# Deel_4_op_amp.net
KiCad netlist of a schematic drawn in Altium Designer
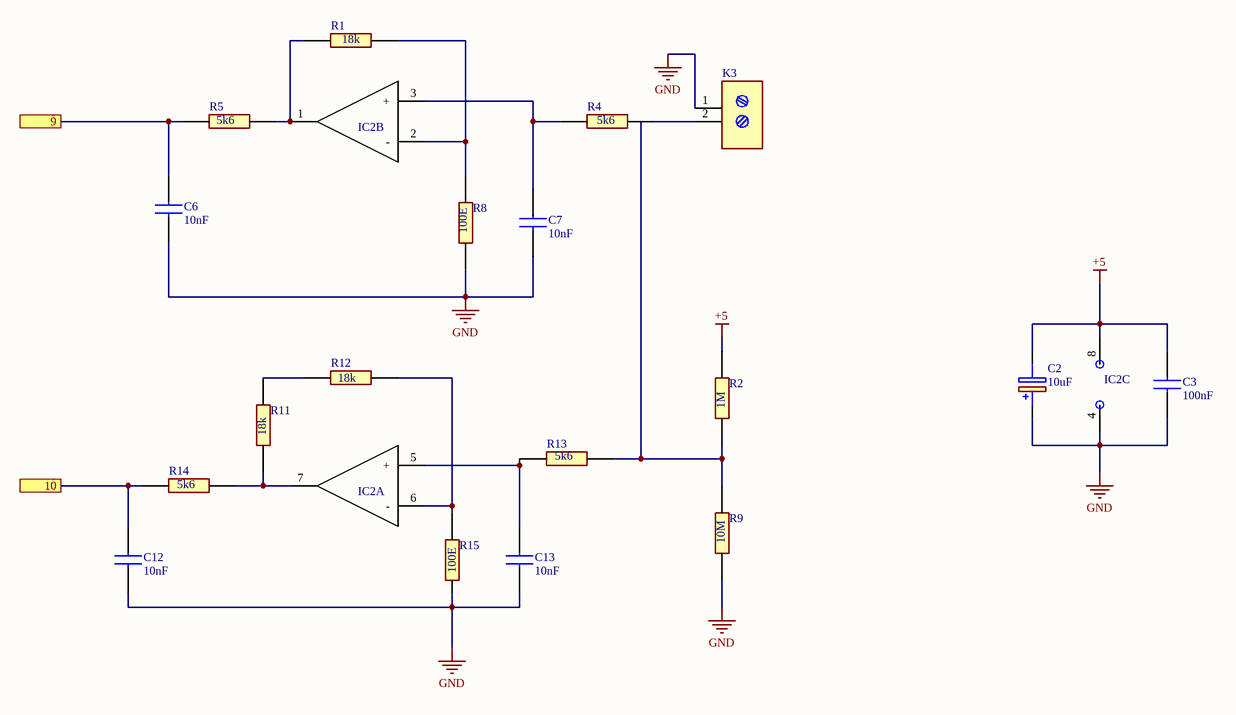
[diagram p0: Deel_4_op_amp.SchDoc]

(export (version "E")
  (design (tool "Eeschema 10.0.6"))
  (components
    (comp (ref "C2")
      (value "10uF")
      (footprint "PcbLib1:10uf")
      (description "Capacitor Polarised 860020672010")
      (fields
        (field (name "MOUSER2 PART NUMBER") "710-860020672010")
        (field (name "MANUFACTURER_PART_NUMBER") "860020672010")
      )
      (libsource (lib "Schlib_soldeerstation") (part "10uF"))
    )
    (comp (ref "C3")
      (value "100nF")
      (footprint "PcbLib1:100nF")
      (description "Capacitor")
      (fields
        (field (name "MANUFACTURER_PART_NUMBER") "0402YC104MAT2A")
        (field (name "MOUSER PART NUMBER") "581-0402YC104MAT2A")
      )
      (libsource (lib "Schlib_soldeerstation") (part "100nF"))
    )
    (comp (ref "C6")
      (value "10nF")
      (footprint "PcbLib1:10nF")
      (description "Capacitor")
      (fields
        (field (name "MANUFACTURER_PART_NUMBER") "0402YC104MAT2A")
        (field (name "MOUSER PART NUMBER") "581-0402YC104MAT2A")
      )
      (libsource (lib "Schlib_soldeerstation") (part "10nF"))
    )
    (comp (ref "C7")
      (value "10nF")
      (footprint "PcbLib1:10nF")
      (description "Capacitor")
      (fields
        (field (name "MANUFACTURER_PART_NUMBER") "0402YC104MAT2A")
        (field (name "MOUSER PART NUMBER") "581-0402YC104MAT2A")
      )
      (libsource (lib "Schlib_soldeerstation") (part "10nF"))
    )
    (comp (ref "C12")
      (value "10nF")
      (footprint "PcbLib1:10nF")
      (description "Capacitor")
      (fields
        (field (name "MANUFACTURER_PART_NUMBER") "0402YC104MAT2A")
        (field (name "MOUSER PART NUMBER") "581-0402YC104MAT2A")
      )
      (libsource (lib "Schlib_soldeerstation") (part "10nF"))
    )
    (comp (ref "C13")
      (value "10nF")
      (footprint "PcbLib1:10nF")
      (description "Capacitor")
      (fields
        (field (name "MANUFACTURER_PART_NUMBER") "0402YC104MAT2A")
        (field (name "MOUSER PART NUMBER") "581-0402YC104MAT2A")
      )
      (libsource (lib "Schlib_soldeerstation") (part "10nF"))
    )
    (comp (ref "IC2")
      (value "MCP6002-E_P dual opamp")
      (footprint "PcbLib1:mcp6002")
      (description "Integrated Circuit")
      (fields
        (field (name "MOUSER2 PART NUMBER") "579-MCP6002-E/P")
        (field (name "MANUFACTURER_PART_NUMBER") "MCP6002-E/P")
      )
      (libsource (lib "Schlib_soldeerstation") (part "MCP6002-E_P dual opamp"))
    )
    (comp (ref "K3")
      (value "schroefconnector")
      (footprint "PcbLib1:schroefconnector")
      (description "Connector 1716020000")
      (fields (field (name "MANUFACTURER_PART_NUMBER") "1716020000"))
      (libsource (lib "Schlib_soldeerstation") (part "schroefconnector"))
    )
    (comp (ref "R1")
      (value "18k")
      (footprint "PcbLib1:18k")
      (description "Resistor")
      (fields
        (field (name "MANUFACTURER_PART_NUMBER") "CPF0805B100RE1")
        (field (name "MOUSER PART NUMBER") "279-CPF0805B100RE1")
      )
      (libsource (lib "Schlib_soldeerstation") (part "18k"))
    )
    (comp (ref "R2")
      (value "1M")
      (footprint "PcbLib1:1M")
      (description "Resistor")
      (fields
        (field (name "MANUFACTURER_PART_NUMBER") "CPF0805B100RE1")
        (field (name "MOUSER PART NUMBER") "279-CPF0805B100RE1")
      )
      (libsource (lib "Schlib_soldeerstation") (part "1M"))
    )
    (comp (ref "R4")
      (value "5k6")
      (footprint "PcbLib1:5k6")
      (description "Resistor")
      (fields
        (field (name "MANUFACTURER_PART_NUMBER") "CPF0805B100RE1")
        (field (name "MOUSER PART NUMBER") "279-CPF0805B100RE1")
      )
      (libsource (lib "Schlib_soldeerstation") (part "5k6"))
    )
    (comp (ref "R5")
      (value "5k6")
      (footprint "PcbLib1:5k6")
      (description "Resistor")
      (fields
        (field (name "MANUFACTURER_PART_NUMBER") "CPF0805B100RE1")
        (field (name "MOUSER PART NUMBER") "279-CPF0805B100RE1")
      )
      (libsource (lib "Schlib_soldeerstation") (part "5k6"))
    )
    (comp (ref "R8")
      (value "100E")
      (footprint "PcbLib1:100ohm")
      (description "Resistor")
      (fields
        (field (name "MANUFACTURER_PART_NUMBER") "CPF0805B100RE1")
        (field (name "MOUSER PART NUMBER") "279-CPF0805B100RE1")
      )
      (libsource (lib "Schlib_soldeerstation") (part "100ohm"))
    )
    (comp (ref "R9")
      (value "10M")
      (footprint "PcbLib1:10M")
      (description "Resistor")
      (fields
        (field (name "MANUFACTURER_PART_NUMBER") "CPF0805B100RE1")
        (field (name "MOUSER PART NUMBER") "279-CPF0805B100RE1")
      )
      (libsource (lib "Schlib_soldeerstation") (part "10M"))
    )
    (comp (ref "R11")
      (value "18k")
      (footprint "PcbLib1:18k")
      (description "Resistor")
      (fields
        (field (name "MANUFACTURER_PART_NUMBER") "CPF0805B100RE1")
        (field (name "MOUSER PART NUMBER") "279-CPF0805B100RE1")
      )
      (libsource (lib "") (part "18k_1"))
    )
    (comp (ref "R12")
      (value "18k")
      (footprint "PcbLib1:18k")
      (description "Resistor")
      (fields
        (field (name "MANUFACTURER_PART_NUMBER") "CPF0805B100RE1")
        (field (name "MOUSER PART NUMBER") "279-CPF0805B100RE1")
      )
      (libsource (lib "Schlib_soldeerstation") (part "18k"))
    )
    (comp (ref "R13")
      (value "5k6")
      (footprint "PcbLib1:5k6")
      (description "Resistor")
      (fields
        (field (name "MANUFACTURER_PART_NUMBER") "CPF0805B100RE1")
        (field (name "MOUSER PART NUMBER") "279-CPF0805B100RE1")
      )
      (libsource (lib "Schlib_soldeerstation") (part "5k6"))
    )
    (comp (ref "R14")
      (value "5k6")
      (footprint "PcbLib1:5k6")
      (description "Resistor")
      (fields
        (field (name "MANUFACTURER_PART_NUMBER") "CPF0805B100RE1")
        (field (name "MOUSER PART NUMBER") "279-CPF0805B100RE1")
      )
      (libsource (lib "Schlib_soldeerstation") (part "5k6"))
    )
    (comp (ref "R15")
      (value "100E")
      (footprint "PcbLib1:100ohm")
      (description "Resistor")
      (fields
        (field (name "MANUFACTURER_PART_NUMBER") "CPF0805B100RE1")
        (field (name "MOUSER PART NUMBER") "279-CPF0805B100RE1")
      )
      (libsource (lib "Schlib_soldeerstation") (part "100ohm"))
    )
  )
  (nets
    (net (code "1") (name "+5") (class "Default")
      (node (ref "C2") (pin "2") (pinfunction "-_2") (pintype "passive"))
      (node (ref "C3") (pin "2") (pinfunction "2_2") (pintype "passive"))
      (node (ref "R2") (pin "2") (pinfunction "2_2") (pintype "passive"))
    )
    (net (code "2") (name "/9") (class "Default")
      (node (ref "C6") (pin "2") (pinfunction "2_2") (pintype "passive"))
      (node (ref "R5") (pin "1") (pinfunction "1_1") (pintype "passive"))
    )
    (net (code "3") (name "/10") (class "Default")
      (node (ref "C12") (pin "2") (pinfunction "2_2") (pintype "passive"))
      (node (ref "R14") (pin "1") (pinfunction "1_1") (pintype "passive"))
    )
    (net (code "4") (name "GND") (class "Default")
      (node (ref "C12") (pin "1") (pinfunction "1_1") (pintype "passive"))
      (node (ref "C13") (pin "1") (pinfunction "1_1") (pintype "passive"))
      (node (ref "C2") (pin "1") (pinfunction "+_1") (pintype "passive"))
      (node (ref "C3") (pin "1") (pinfunction "1_1") (pintype "passive"))
      (node (ref "C6") (pin "1") (pinfunction "1_1") (pintype "passive"))
      (node (ref "C7") (pin "1") (pinfunction "1_1") (pintype "passive"))
      (node (ref "K3") (pin "1") (pinfunction "1_1") (pintype "passive"))
      (node (ref "R15") (pin "1") (pinfunction "1_1") (pintype "passive"))
      (node (ref "R8") (pin "1") (pinfunction "1_1") (pintype "passive"))
      (node (ref "R9") (pin "1") (pinfunction "1_1") (pintype "passive"))
    )
    (net (code "5") (name "Net-(IC2A-+)") (class "Default")
      (node (ref "C13") (pin "2") (pinfunction "2_2") (pintype "passive"))
      (node (ref "IC2") (pin "5") (pinfunction "+_5") (pintype "passive"))
      (node (ref "R13") (pin "1") (pinfunction "1_1") (pintype "passive"))
    )
    (net (code "6") (name "Net-(IC2A--)") (class "Default")
      (node (ref "IC2") (pin "6") (pinfunction "-_6") (pintype "passive"))
      (node (ref "R12") (pin "2") (pinfunction "2_2") (pintype "passive"))
      (node (ref "R15") (pin "2") (pinfunction "2_2") (pintype "passive"))
    )
    (net (code "7") (name "Net-(IC2A-VOUTB)") (class "Default")
      (node (ref "IC2") (pin "7") (pinfunction "VOUTB_7") (pintype "passive"))
      (node (ref "R11") (pin "1") (pinfunction "1_1") (pintype "passive"))
      (node (ref "R14") (pin "2") (pinfunction "2_2") (pintype "passive"))
    )
    (net (code "8") (name "Net-(IC2B-+)") (class "Default")
      (node (ref "C7") (pin "2") (pinfunction "2_2") (pintype "passive"))
      (node (ref "IC2") (pin "3") (pinfunction "+_3") (pintype "passive"))
      (node (ref "R4") (pin "1") (pinfunction "1_1") (pintype "passive"))
    )
    (net (code "9") (name "Net-(IC2B--)") (class "Default")
      (node (ref "IC2") (pin "2") (pinfunction "-_2") (pintype "passive"))
      (node (ref "R1") (pin "2") (pinfunction "2_2") (pintype "passive"))
      (node (ref "R8") (pin "2") (pinfunction "2_2") (pintype "passive"))
    )
    (net (code "10") (name "Net-(IC2B-VOUTA)") (class "Default")
      (node (ref "IC2") (pin "1") (pinfunction "VOUTA_1") (pintype "passive"))
      (node (ref "R1") (pin "1") (pinfunction "1_1") (pintype "passive"))
      (node (ref "R5") (pin "2") (pinfunction "2_2") (pintype "passive"))
    )
    (net (code "11") (name "Net-(K3-Pad2)") (class "Default")
      (node (ref "K3") (pin "2") (pinfunction "2_2") (pintype "passive"))
      (node (ref "R4") (pin "2") (pinfunction "2_2") (pintype "passive"))
    )
    (net (code "12") (name "Net-(R11-Pad2)") (class "Default")
      (node (ref "R11") (pin "2") (pinfunction "2_2") (pintype "passive"))
      (node (ref "R12") (pin "1") (pinfunction "1_1") (pintype "passive"))
    )
    (net (code "13") (name "Net-(R13-Pad2)") (class "Default")
      (node (ref "R13") (pin "2") (pinfunction "2_2") (pintype "passive"))
      (node (ref "R2") (pin "1") (pinfunction "1_1") (pintype "passive"))
      (node (ref "R9") (pin "2") (pinfunction "2_2") (pintype "passive"))
    )
    (net (code "14") (name "unconnected-(IC2C-VDD-Pad8)") (class "Default")
      (node (ref "IC2") (pin "8") (pinfunction "VDD_8") (pintype "passive"))
    )
    (net (code "15") (name "unconnected-(IC2C-VSS-Pad4)") (class "Default")
      (node (ref "IC2") (pin "4") (pinfunction "VSS_4") (pintype "passive"))
    )
  )
)
